# PPMB32-E.net
KiCad netlist of a schematic drawn in EAGLE
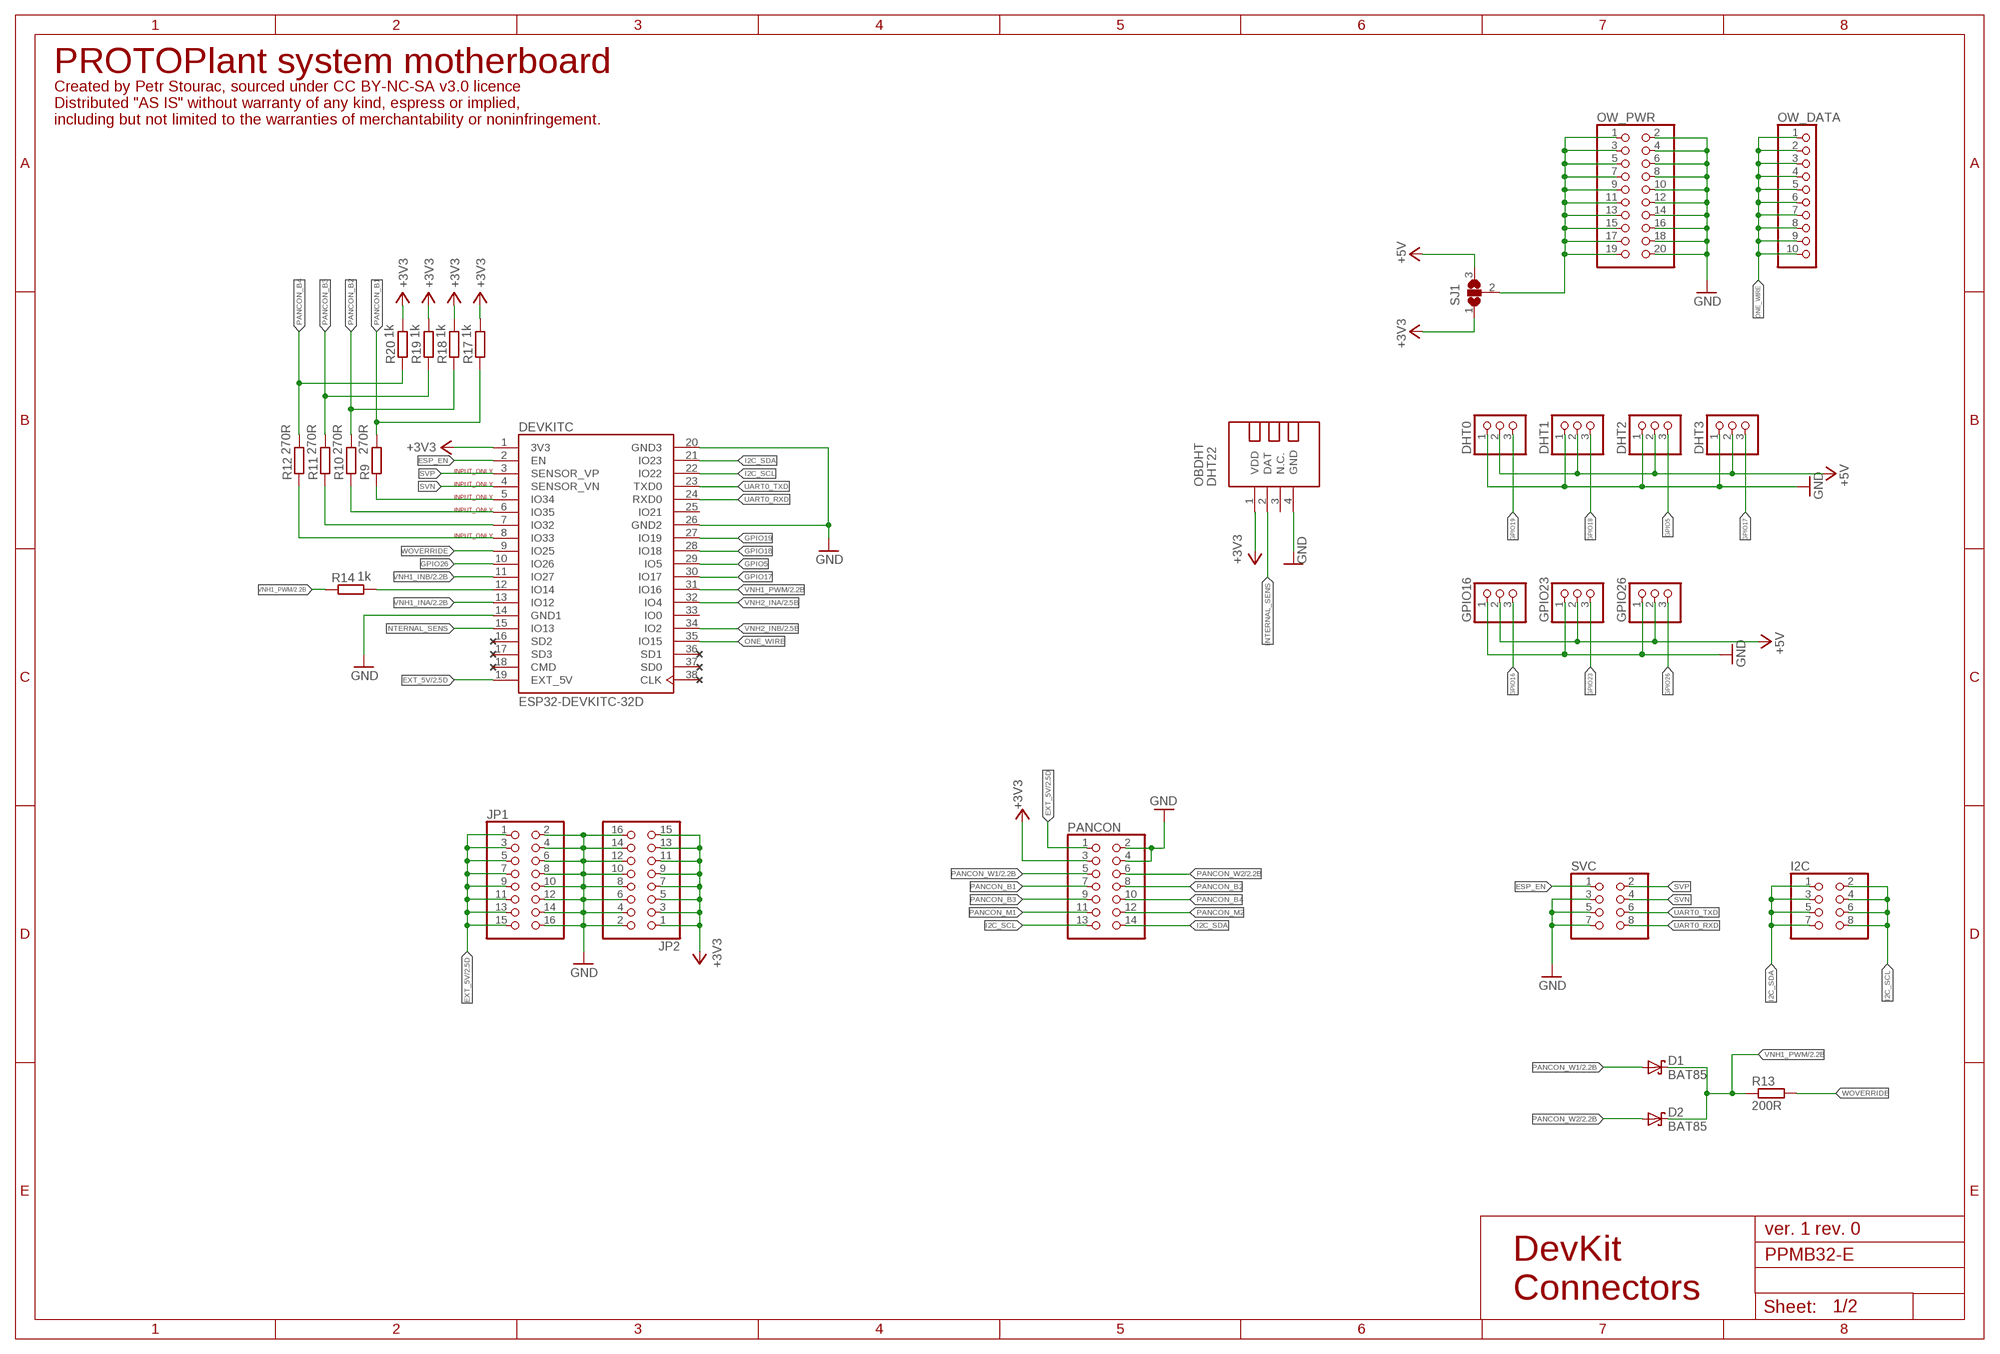
[diagram p0: schematic, sheet 1]
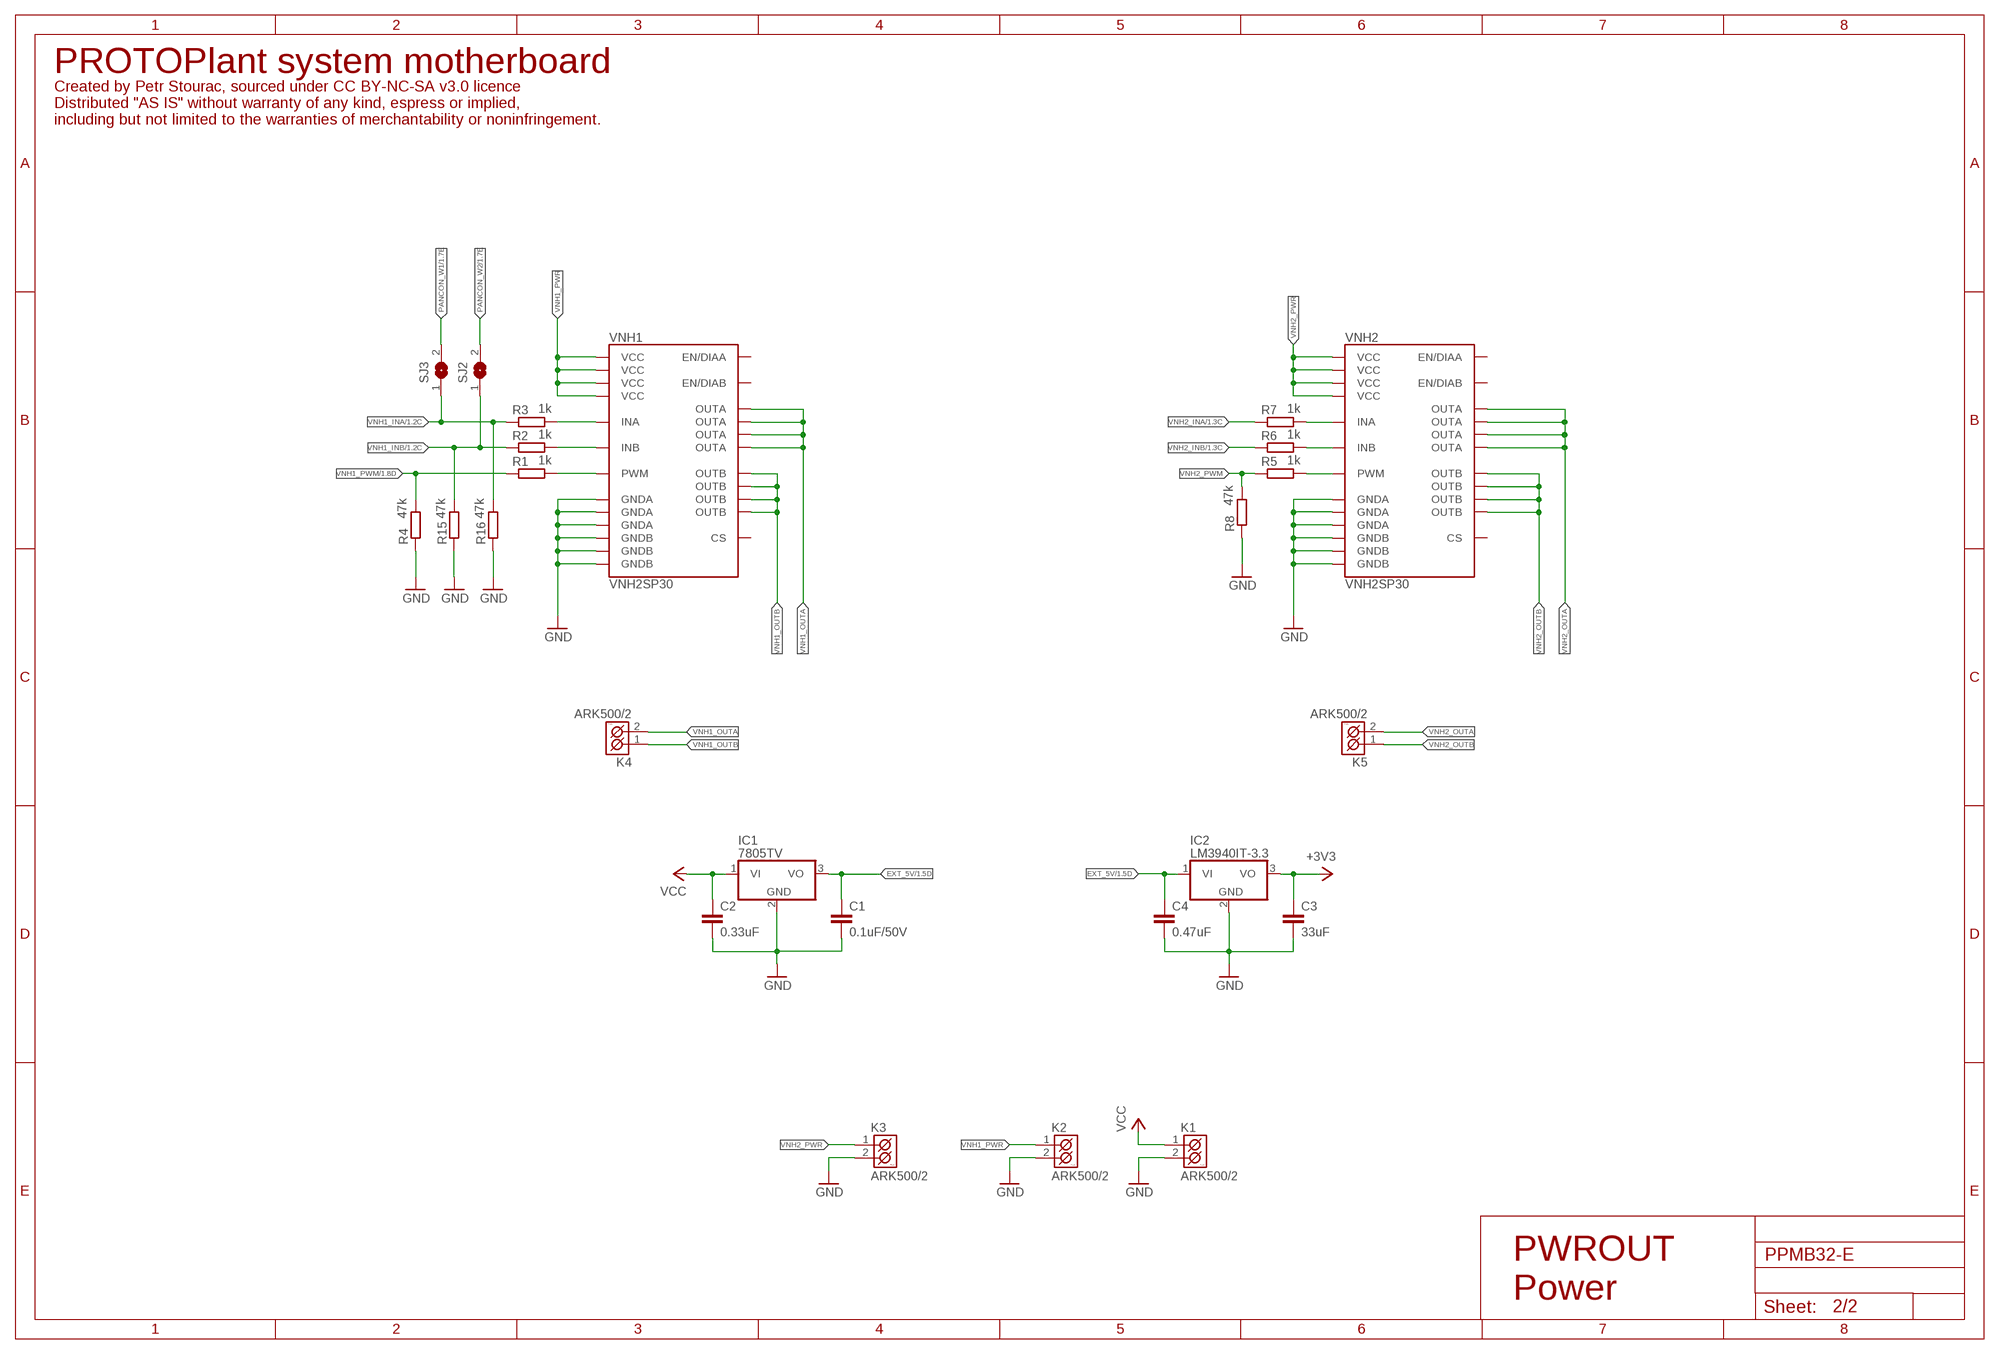
[diagram p1: schematic, sheet 2]

(export (version "E")
  (design (tool "Eeschema 10.0.6"))
  (components
    (comp (ref "D1")
      (value "BAT85")
      (footprint "eagle-import:DO35-7")
      (libsource (lib "eagle-import") (part "SCHOTTKY-DIODEDO35-7"))
    )
    (comp (ref "D2")
      (value "BAT85")
      (footprint "eagle-import:DO35-7")
      (libsource (lib "eagle-import") (part "SCHOTTKY-DIODEDO35-7"))
    )
    (comp (ref "DEVKITC")
      (value "ESP32-DEVKITC-32D")
      (footprint "eagle-import:MODULE_ESP32-DEVKITC-32D")
      (fields (field (name "MF") "Espressif Systems"))
      (libsource (lib "eagle-import") (part "ESP32-DEVKITC-32D"))
    )
    (comp (ref "DHT0")
      (value "PINHD-1X3")
      (footprint "eagle-import:1X03")
      (libsource (lib "eagle-import") (part "PINHD-1X3"))
    )
    (comp (ref "DHT1")
      (value "PINHD-1X3")
      (footprint "eagle-import:1X03")
      (libsource (lib "eagle-import") (part "PINHD-1X3"))
    )
    (comp (ref "DHT2")
      (value "PINHD-1X3")
      (footprint "eagle-import:1X03")
      (libsource (lib "eagle-import") (part "PINHD-1X3"))
    )
    (comp (ref "DHT3")
      (value "PINHD-1X3")
      (footprint "eagle-import:1X03")
      (libsource (lib "eagle-import") (part "PINHD-1X3"))
    )
    (comp (ref "GPIO16")
      (value "PINHD-1X3")
      (footprint "eagle-import:1X03")
      (libsource (lib "eagle-import") (part "PINHD-1X3"))
    )
    (comp (ref "GPIO23")
      (value "PINHD-1X3")
      (footprint "eagle-import:1X03")
      (libsource (lib "eagle-import") (part "PINHD-1X3"))
    )
    (comp (ref "GPIO26")
      (value "PINHD-1X3")
      (footprint "eagle-import:1X03")
      (libsource (lib "eagle-import") (part "PINHD-1X3"))
    )
    (comp (ref "I2C")
      (value "PINHD-2X4")
      (footprint "eagle-import:2X04")
      (libsource (lib "eagle-import") (part "PINHD-2X4"))
    )
    (comp (ref "JP1")
      (value "PINHD-2X8")
      (footprint "eagle-import:2X08")
      (libsource (lib "eagle-import") (part "PINHD-2X8"))
    )
    (comp (ref "JP2")
      (value "PINHD-2X8")
      (footprint "eagle-import:2X08")
      (libsource (lib "eagle-import") (part "PINHD-2X8"))
    )
    (comp (ref "OBDHT")
      (value "DHT22")
      (footprint "eagle-import:TEMP-HUM-SENSOR-DHT22")
      (libsource (lib "eagle-import") (part "TEMP-HUM-SENSOR-DHT22"))
    )
    (comp (ref "OW_DATA")
      (value "PINHD-1X10")
      (footprint "eagle-import:1X10")
      (libsource (lib "eagle-import") (part "PINHD-1X10"))
    )
    (comp (ref "OW_PWR")
      (value "PINHD-2X10")
      (footprint "eagle-import:2X10")
      (libsource (lib "eagle-import") (part "PINHD-2X10"))
    )
    (comp (ref "PANCON")
      (value "PINHD-2X7")
      (footprint "eagle-import:2X07")
      (libsource (lib "eagle-import") (part "PINHD-2X7"))
    )
    (comp (ref "R9")
      (value "270R")
      (footprint "eagle-import:R0603")
      (libsource (lib "eagle-import") (part "R-EU_R0603"))
    )
    (comp (ref "R10")
      (value "270R")
      (footprint "eagle-import:R0603")
      (libsource (lib "eagle-import") (part "R-EU_R0603"))
    )
    (comp (ref "R11")
      (value "270R")
      (footprint "eagle-import:R0603")
      (libsource (lib "eagle-import") (part "R-EU_R0603"))
    )
    (comp (ref "R12")
      (value "270R")
      (footprint "eagle-import:R0603")
      (libsource (lib "eagle-import") (part "R-EU_R0603"))
    )
    (comp (ref "R13")
      (value "200R")
      (footprint "eagle-import:R0603")
      (libsource (lib "eagle-import") (part "R-EU_R0603"))
    )
    (comp (ref "R14")
      (value "1k")
      (footprint "eagle-import:R0603")
      (libsource (lib "eagle-import") (part "R-EU_R0603"))
    )
    (comp (ref "R17")
      (value "1k")
      (footprint "eagle-import:R0603")
      (libsource (lib "eagle-import") (part "R-EU_R0603"))
    )
    (comp (ref "R18")
      (value "1k")
      (footprint "eagle-import:R0603")
      (libsource (lib "eagle-import") (part "R-EU_R0603"))
    )
    (comp (ref "R19")
      (value "1k")
      (footprint "eagle-import:R0603")
      (libsource (lib "eagle-import") (part "R-EU_R0603"))
    )
    (comp (ref "R20")
      (value "1k")
      (footprint "eagle-import:R0603")
      (libsource (lib "eagle-import") (part "R-EU_R0603"))
    )
    (comp (ref "SJ1")
      (value "SJ2W")
      (footprint "eagle-import:SJ_2")
      (libsource (lib "eagle-import") (part "SJ2W"))
    )
    (comp (ref "SVC")
      (value "PINHD-2X4")
      (footprint "eagle-import:2X04")
      (libsource (lib "eagle-import") (part "PINHD-2X4"))
    )
    (comp (ref "C1")
      (value "0.1uF/50V")
      (footprint "eagle-import:C1206K")
      (libsource (lib "eagle-import") (part "C-EUC1206K"))
    )
    (comp (ref "C2")
      (value "0.33uF")
      (footprint "eagle-import:C1206K")
      (libsource (lib "eagle-import") (part "C-EUC1206K"))
    )
    (comp (ref "C3")
      (value "33uF")
      (footprint "eagle-import:C1206K")
      (libsource (lib "eagle-import") (part "C-EUC1206K"))
    )
    (comp (ref "C4")
      (value "0.47uF")
      (footprint "eagle-import:C1206K")
      (libsource (lib "eagle-import") (part "C-EUC1206K"))
    )
    (comp (ref "IC1")
      (value "7805TV")
      (footprint "eagle-import:TO220V")
      (libsource (lib "eagle-import") (part "78TV05"))
    )
    (comp (ref "IC2")
      (value "LM3940IT-3.3")
      (footprint "eagle-import:TO220V")
      (libsource (lib "eagle-import") (part "78TV8"))
    )
    (comp (ref "K1")
      (value "ARK500/2")
      (footprint "eagle-import:ARK500_2")
      (libsource (lib "eagle-import") (part "ARK500/2"))
    )
    (comp (ref "K2")
      (value "ARK500/2")
      (footprint "eagle-import:ARK500_2")
      (libsource (lib "eagle-import") (part "ARK500/2"))
    )
    (comp (ref "K3")
      (value "ARK500/2")
      (footprint "eagle-import:ARK500_2")
      (libsource (lib "eagle-import") (part "ARK500/2"))
    )
    (comp (ref "K4")
      (value "ARK500/2")
      (footprint "eagle-import:ARK500_2")
      (libsource (lib "eagle-import") (part "ARK500/2"))
    )
    (comp (ref "K5")
      (value "ARK500/2")
      (footprint "eagle-import:ARK500_2")
      (libsource (lib "eagle-import") (part "ARK500/2"))
    )
    (comp (ref "R1")
      (value "1k")
      (footprint "eagle-import:R0603")
      (libsource (lib "eagle-import") (part "R-EU_R0603"))
    )
    (comp (ref "R2")
      (value "1k")
      (footprint "eagle-import:R0603")
      (libsource (lib "eagle-import") (part "R-EU_R0603"))
    )
    (comp (ref "R3")
      (value "1k")
      (footprint "eagle-import:R0603")
      (libsource (lib "eagle-import") (part "R-EU_R0603"))
    )
    (comp (ref "R4")
      (value "47k")
      (footprint "eagle-import:R0603")
      (libsource (lib "eagle-import") (part "R-EU_R0603"))
    )
    (comp (ref "R5")
      (value "1k")
      (footprint "eagle-import:R0603")
      (libsource (lib "eagle-import") (part "R-EU_R0603"))
    )
    (comp (ref "R6")
      (value "1k")
      (footprint "eagle-import:R0603")
      (libsource (lib "eagle-import") (part "R-EU_R0603"))
    )
    (comp (ref "R7")
      (value "1k")
      (footprint "eagle-import:R0603")
      (libsource (lib "eagle-import") (part "R-EU_R0603"))
    )
    (comp (ref "R8")
      (value "47k")
      (footprint "eagle-import:R0603")
      (libsource (lib "eagle-import") (part "R-EU_R0603"))
    )
    (comp (ref "R15")
      (value "47k")
      (footprint "eagle-import:R0603")
      (libsource (lib "eagle-import") (part "R-EU_R0603"))
    )
    (comp (ref "R16")
      (value "47k")
      (footprint "eagle-import:R0603")
      (libsource (lib "eagle-import") (part "R-EU_R0603"))
    )
    (comp (ref "SJ2") (value "SJ") (footprint "eagle-import:SJ") (libsource (lib "eagle-import") (part "SJ")))
    (comp (ref "SJ3") (value "SJ") (footprint "eagle-import:SJ") (libsource (lib "eagle-import") (part "SJ")))
    (comp (ref "VNH1")
      (value "VNH2SP30")
      (footprint "eagle-import:VNH2SP30")
      (libsource (lib "eagle-import") (part "VNH2SP30"))
    )
    (comp (ref "VNH2")
      (value "VNH2SP30")
      (footprint "eagle-import:VNH2SP30")
      (libsource (lib "eagle-import") (part "VNH2SP30"))
    )
  )
  (nets
    (net (code "1") (name "+3V3") (class "Default")
      (node (ref "C3") (pin "1") (pinfunction "1_1") (pintype "passive"))
      (node (ref "DEVKITC") (pin "1") (pinfunction "3V3_1") (pintype "power_in"))
      (node (ref "IC2") (pin "3") (pinfunction "VO_3") (pintype "passive"))
      (node (ref "JP2") (pin "1") (pinfunction "1_1") (pintype "passive"))
      (node (ref "JP2") (pin "11") (pinfunction "11_11") (pintype "passive"))
      (node (ref "JP2") (pin "13") (pinfunction "13_13") (pintype "passive"))
      (node (ref "JP2") (pin "15") (pinfunction "15_15") (pintype "passive"))
      (node (ref "JP2") (pin "3") (pinfunction "3_3") (pintype "passive"))
      (node (ref "JP2") (pin "5") (pinfunction "5_5") (pintype "passive"))
      (node (ref "JP2") (pin "7") (pinfunction "7_7") (pintype "passive"))
      (node (ref "JP2") (pin "9") (pinfunction "9_9") (pintype "passive"))
      (node (ref "OBDHT") (pin "1") (pinfunction "VDD_1") (pintype "power_in"))
      (node (ref "PANCON") (pin "3") (pinfunction "3_3") (pintype "passive"))
      (node (ref "R17") (pin "2") (pinfunction "2_2") (pintype "passive"))
      (node (ref "R18") (pin "2") (pinfunction "2_2") (pintype "passive"))
      (node (ref "R19") (pin "2") (pinfunction "2_2") (pintype "passive"))
      (node (ref "R20") (pin "2") (pinfunction "2_2") (pintype "passive"))
      (node (ref "SJ1") (pin "1") (pinfunction "1_1") (pintype "passive"))
    )
    (net (code "2") (name "+5V") (class "Default")
      (node (ref "DHT0") (pin "2") (pinfunction "2_2") (pintype "passive"))
      (node (ref "DHT1") (pin "2") (pinfunction "2_2") (pintype "passive"))
      (node (ref "DHT2") (pin "2") (pinfunction "2_2") (pintype "passive"))
      (node (ref "DHT3") (pin "2") (pinfunction "2_2") (pintype "passive"))
      (node (ref "GPIO16") (pin "2") (pinfunction "2_2") (pintype "passive"))
      (node (ref "GPIO23") (pin "2") (pinfunction "2_2") (pintype "passive"))
      (node (ref "GPIO26") (pin "2") (pinfunction "2_2") (pintype "passive"))
      (node (ref "SJ1") (pin "3") (pinfunction "3_3") (pintype "passive"))
    )
    (net (code "3") (name "ESP_EN") (class "Default")
      (node (ref "DEVKITC") (pin "2") (pinfunction "EN_2") (pintype "input"))
      (node (ref "SVC") (pin "1") (pinfunction "1_1") (pintype "passive"))
    )
    (net (code "4") (name "EXT_5V") (class "Default")
      (node (ref "C1") (pin "1") (pinfunction "1_1") (pintype "passive"))
      (node (ref "C4") (pin "1") (pinfunction "1_1") (pintype "passive"))
      (node (ref "DEVKITC") (pin "19") (pinfunction "EXT_5V_19") (pintype "power_in"))
      (node (ref "IC1") (pin "3") (pinfunction "VO_3") (pintype "passive"))
      (node (ref "IC2") (pin "1") (pinfunction "VI_1") (pintype "input"))
      (node (ref "JP1") (pin "1") (pinfunction "1_1") (pintype "passive"))
      (node (ref "JP1") (pin "11") (pinfunction "11_11") (pintype "passive"))
      (node (ref "JP1") (pin "13") (pinfunction "13_13") (pintype "passive"))
      (node (ref "JP1") (pin "15") (pinfunction "15_15") (pintype "passive"))
      (node (ref "JP1") (pin "3") (pinfunction "3_3") (pintype "passive"))
      (node (ref "JP1") (pin "5") (pinfunction "5_5") (pintype "passive"))
      (node (ref "JP1") (pin "7") (pinfunction "7_7") (pintype "passive"))
      (node (ref "JP1") (pin "9") (pinfunction "9_9") (pintype "passive"))
      (node (ref "PANCON") (pin "1") (pinfunction "1_1") (pintype "passive"))
    )
    (net (code "5") (name "GND") (class "Default")
      (node (ref "C1") (pin "2") (pinfunction "2_2") (pintype "passive"))
      (node (ref "C2") (pin "2") (pinfunction "2_2") (pintype "passive"))
      (node (ref "C3") (pin "2") (pinfunction "2_2") (pintype "passive"))
      (node (ref "C4") (pin "2") (pinfunction "2_2") (pintype "passive"))
      (node (ref "DEVKITC") (pin "14") (pinfunction "GND1_14") (pintype "power_in"))
      (node (ref "DEVKITC") (pin "20") (pinfunction "GND3_20") (pintype "power_in"))
      (node (ref "DEVKITC") (pin "26") (pinfunction "GND2_26") (pintype "power_in"))
      (node (ref "DHT0") (pin "1") (pinfunction "1_1") (pintype "passive"))
      (node (ref "DHT1") (pin "1") (pinfunction "1_1") (pintype "passive"))
      (node (ref "DHT2") (pin "1") (pinfunction "1_1") (pintype "passive"))
      (node (ref "DHT3") (pin "1") (pinfunction "1_1") (pintype "passive"))
      (node (ref "GPIO16") (pin "1") (pinfunction "1_1") (pintype "passive"))
      (node (ref "GPIO23") (pin "1") (pinfunction "1_1") (pintype "passive"))
      (node (ref "GPIO26") (pin "1") (pinfunction "1_1") (pintype "passive"))
      (node (ref "IC1") (pin "2") (pinfunction "GND_2") (pintype "passive"))
      (node (ref "IC2") (pin "2") (pinfunction "GND_2") (pintype "passive"))
      (node (ref "JP1") (pin "10") (pinfunction "10_10") (pintype "passive"))
      (node (ref "JP1") (pin "12") (pinfunction "12_12") (pintype "passive"))
      (node (ref "JP1") (pin "14") (pinfunction "14_14") (pintype "passive"))
      (node (ref "JP1") (pin "16") (pinfunction "16_16") (pintype "passive"))
      (node (ref "JP1") (pin "2") (pinfunction "2_2") (pintype "passive"))
      (node (ref "JP1") (pin "4") (pinfunction "4_4") (pintype "passive"))
      (node (ref "JP1") (pin "6") (pinfunction "6_6") (pintype "passive"))
      (node (ref "JP1") (pin "8") (pinfunction "8_8") (pintype "passive"))
      (node (ref "JP2") (pin "10") (pinfunction "10_10") (pintype "passive"))
      (node (ref "JP2") (pin "12") (pinfunction "12_12") (pintype "passive"))
      (node (ref "JP2") (pin "14") (pinfunction "14_14") (pintype "passive"))
      (node (ref "JP2") (pin "16") (pinfunction "16_16") (pintype "passive"))
      (node (ref "JP2") (pin "2") (pinfunction "2_2") (pintype "passive"))
      (node (ref "JP2") (pin "4") (pinfunction "4_4") (pintype "passive"))
      (node (ref "JP2") (pin "6") (pinfunction "6_6") (pintype "passive"))
      (node (ref "JP2") (pin "8") (pinfunction "8_8") (pintype "passive"))
      (node (ref "K1") (pin "2") (pinfunction "K2_2") (pintype "passive"))
      (node (ref "K2") (pin "2") (pinfunction "K2_2") (pintype "passive"))
      (node (ref "K3") (pin "2") (pinfunction "K2_2") (pintype "passive"))
      (node (ref "OBDHT") (pin "4") (pinfunction "GND_4") (pintype "power_in"))
      (node (ref "OW_PWR") (pin "10") (pinfunction "10_10") (pintype "passive"))
      (node (ref "OW_PWR") (pin "12") (pinfunction "12_12") (pintype "passive"))
      (node (ref "OW_PWR") (pin "14") (pinfunction "14_14") (pintype "passive"))
      (node (ref "OW_PWR") (pin "16") (pinfunction "16_16") (pintype "passive"))
      (node (ref "OW_PWR") (pin "18") (pinfunction "18_18") (pintype "passive"))
      (node (ref "OW_PWR") (pin "2") (pinfunction "2_2") (pintype "passive"))
      (node (ref "OW_PWR") (pin "20") (pinfunction "20_20") (pintype "passive"))
      (node (ref "OW_PWR") (pin "4") (pinfunction "4_4") (pintype "passive"))
      (node (ref "OW_PWR") (pin "6") (pinfunction "6_6") (pintype "passive"))
      (node (ref "OW_PWR") (pin "8") (pinfunction "8_8") (pintype "passive"))
      (node (ref "PANCON") (pin "2") (pinfunction "2_2") (pintype "passive"))
      (node (ref "PANCON") (pin "4") (pinfunction "4_4") (pintype "passive"))
      (node (ref "R15") (pin "1") (pinfunction "1_1") (pintype "passive"))
      (node (ref "R16") (pin "1") (pinfunction "1_1") (pintype "passive"))
      (node (ref "R4") (pin "1") (pinfunction "1_1") (pintype "passive"))
      (node (ref "R8") (pin "1") (pinfunction "1_1") (pintype "passive"))
      (node (ref "SVC") (pin "3") (pinfunction "3_3") (pintype "passive"))
      (node (ref "SVC") (pin "5") (pinfunction "5_5") (pintype "passive"))
      (node (ref "SVC") (pin "7") (pinfunction "7_7") (pintype "passive"))
      (node (ref "VNH1") (pin "18") (pinfunction "GNDB_18") (pintype "bidirectional"))
      (node (ref "VNH1") (pin "19") (pinfunction "GNDB_19") (pintype "bidirectional"))
      (node (ref "VNH1") (pin "20") (pinfunction "GNDB_20") (pintype "bidirectional"))
      (node (ref "VNH1") (pin "26") (pinfunction "GNDA_26") (pintype "bidirectional"))
      (node (ref "VNH1") (pin "27") (pinfunction "GNDA_27") (pintype "bidirectional"))
      (node (ref "VNH1") (pin "28") (pinfunction "GNDA_28") (pintype "bidirectional"))
      (node (ref "VNH2") (pin "18") (pinfunction "GNDB_18") (pintype "bidirectional"))
      (node (ref "VNH2") (pin "19") (pinfunction "GNDB_19") (pintype "bidirectional"))
      (node (ref "VNH2") (pin "20") (pinfunction "GNDB_20") (pintype "bidirectional"))
      (node (ref "VNH2") (pin "26") (pinfunction "GNDA_26") (pintype "bidirectional"))
      (node (ref "VNH2") (pin "27") (pinfunction "GNDA_27") (pintype "bidirectional"))
      (node (ref "VNH2") (pin "28") (pinfunction "GNDA_28") (pintype "bidirectional"))
    )
    (net (code "6") (name "GPIO5") (class "Default")
      (node (ref "DEVKITC") (pin "29") (pinfunction "IO5_29") (pintype "bidirectional"))
      (node (ref "DHT2") (pin "3") (pinfunction "3_3") (pintype "passive"))
    )
    (net (code "7") (name "GPIO16") (class "Default")
      (node (ref "GPIO16") (pin "3") (pinfunction "3_3") (pintype "passive"))
    )
    (net (code "8") (name "GPIO17") (class "Default")
      (node (ref "DEVKITC") (pin "30") (pinfunction "IO17_30") (pintype "bidirectional"))
      (node (ref "DHT3") (pin "3") (pinfunction "3_3") (pintype "passive"))
    )
    (net (code "9") (name "GPIO18") (class "Default")
      (node (ref "DEVKITC") (pin "28") (pinfunction "IO18_28") (pintype "bidirectional"))
      (node (ref "DHT1") (pin "3") (pinfunction "3_3") (pintype "passive"))
    )
    (net (code "10") (name "GPIO19") (class "Default")
      (node (ref "DEVKITC") (pin "27") (pinfunction "IO19_27") (pintype "bidirectional"))
      (node (ref "DHT0") (pin "3") (pinfunction "3_3") (pintype "passive"))
    )
    (net (code "11") (name "GPIO23") (class "Default")
      (node (ref "GPIO23") (pin "3") (pinfunction "3_3") (pintype "passive"))
    )
    (net (code "12") (name "GPIO26") (class "Default")
      (node (ref "DEVKITC") (pin "10") (pinfunction "IO26_10") (pintype "bidirectional"))
      (node (ref "GPIO26") (pin "3") (pinfunction "3_3") (pintype "passive"))
    )
    (net (code "13") (name "I2C_SCL") (class "Default")
      (node (ref "DEVKITC") (pin "22") (pinfunction "IO22_22") (pintype "bidirectional"))
      (node (ref "I2C") (pin "2") (pinfunction "2_2") (pintype "passive"))
      (node (ref "I2C") (pin "4") (pinfunction "4_4") (pintype "passive"))
      (node (ref "I2C") (pin "6") (pinfunction "6_6") (pintype "passive"))
      (node (ref "I2C") (pin "8") (pinfunction "8_8") (pintype "passive"))
      (node (ref "PANCON") (pin "13") (pinfunction "13_13") (pintype "passive"))
    )
    (net (code "14") (name "I2C_SDA") (class "Default")
      (node (ref "DEVKITC") (pin "21") (pinfunction "IO23_21") (pintype "bidirectional"))
      (node (ref "I2C") (pin "1") (pinfunction "1_1") (pintype "passive"))
      (node (ref "I2C") (pin "3") (pinfunction "3_3") (pintype "passive"))
      (node (ref "I2C") (pin "5") (pinfunction "5_5") (pintype "passive"))
      (node (ref "I2C") (pin "7") (pinfunction "7_7") (pintype "passive"))
      (node (ref "PANCON") (pin "14") (pinfunction "14_14") (pintype "passive"))
    )
    (net (code "15") (name "INTERNAL_SENS") (class "Default")
      (node (ref "DEVKITC") (pin "15") (pinfunction "IO13_15") (pintype "bidirectional"))
      (node (ref "OBDHT") (pin "2") (pinfunction "DAT_2") (pintype "bidirectional"))
    )
    (net (code "16") (name "Net-(DEVKITC-IO14)") (class "Default")
      (node (ref "DEVKITC") (pin "12") (pinfunction "IO14_12") (pintype "bidirectional"))
      (node (ref "R14") (pin "2") (pinfunction "2_2") (pintype "passive"))
    )
    (net (code "17") (name "Net-(DEVKITC-IO32)") (class "Default")
      (node (ref "DEVKITC") (pin "7") (pinfunction "IO32_7") (pintype "bidirectional"))
      (node (ref "R11") (pin "1") (pinfunction "1_1") (pintype "passive"))
    )
    (net (code "18") (name "Net-(DEVKITC-IO33)") (class "Default")
      (node (ref "DEVKITC") (pin "8") (pinfunction "IO33_8") (pintype "bidirectional"))
      (node (ref "R12") (pin "1") (pinfunction "1_1") (pintype "passive"))
    )
    (net (code "19") (name "Net-(DEVKITC-IO34)") (class "Default")
      (node (ref "DEVKITC") (pin "5") (pinfunction "IO34_5") (pintype "bidirectional"))
      (node (ref "R9") (pin "1") (pinfunction "1_1") (pintype "passive"))
    )
    (net (code "20") (name "Net-(DEVKITC-IO35)") (class "Default")
      (node (ref "DEVKITC") (pin "6") (pinfunction "IO35_6") (pintype "bidirectional"))
      (node (ref "R10") (pin "1") (pinfunction "1_1") (pintype "passive"))
    )
    (net (code "21") (name "Net-(OW_PWR-Pad1)") (class "Default")
      (node (ref "OW_PWR") (pin "1") (pinfunction "1_1") (pintype "passive"))
      (node (ref "OW_PWR") (pin "11") (pinfunction "11_11") (pintype "passive"))
      (node (ref "OW_PWR") (pin "13") (pinfunction "13_13") (pintype "passive"))
      (node (ref "OW_PWR") (pin "15") (pinfunction "15_15") (pintype "passive"))
      (node (ref "OW_PWR") (pin "17") (pinfunction "17_17") (pintype "passive"))
      (node (ref "OW_PWR") (pin "19") (pinfunction "19_19") (pintype "passive"))
      (node (ref "OW_PWR") (pin "3") (pinfunction "3_3") (pintype "passive"))
      (node (ref "OW_PWR") (pin "5") (pinfunction "5_5") (pintype "passive"))
      (node (ref "OW_PWR") (pin "7") (pinfunction "7_7") (pintype "passive"))
      (node (ref "OW_PWR") (pin "9") (pinfunction "9_9") (pintype "passive"))
      (node (ref "SJ1") (pin "2") (pinfunction "2_2") (pintype "passive"))
    )
    (net (code "22") (name "Net-(VNH1-INA)") (class "Default")
      (node (ref "R3") (pin "2") (pinfunction "2_2") (pintype "passive"))
      (node (ref "VNH1") (pin "5") (pinfunction "INA_5") (pintype "bidirectional"))
    )
    (net (code "23") (name "Net-(VNH1-INB)") (class "Default")
      (node (ref "R2") (pin "2") (pinfunction "2_2") (pintype "passive"))
      (node (ref "VNH1") (pin "11") (pinfunction "INB_11") (pintype "bidirectional"))
    )
    (net (code "24") (name "Net-(VNH1-PWM)") (class "Default")
      (node (ref "R1") (pin "2") (pinfunction "2_2") (pintype "passive"))
      (node (ref "VNH1") (pin "8") (pinfunction "PWM_8") (pintype "bidirectional"))
    )
    (net (code "25") (name "Net-(VNH2-INA)") (class "Default")
      (node (ref "R7") (pin "2") (pinfunction "2_2") (pintype "passive"))
      (node (ref "VNH2") (pin "5") (pinfunction "INA_5") (pintype "bidirectional"))
    )
    (net (code "26") (name "Net-(VNH2-INB)") (class "Default")
      (node (ref "R6") (pin "2") (pinfunction "2_2") (pintype "passive"))
      (node (ref "VNH2") (pin "11") (pinfunction "INB_11") (pintype "bidirectional"))
    )
    (net (code "27") (name "Net-(VNH2-PWM)") (class "Default")
      (node (ref "R5") (pin "2") (pinfunction "2_2") (pintype "passive"))
      (node (ref "VNH2") (pin "8") (pinfunction "PWM_8") (pintype "bidirectional"))
    )
    (net (code "28") (name "ONE_WIRE") (class "Default")
      (node (ref "DEVKITC") (pin "35") (pinfunction "IO15_35") (pintype "bidirectional"))
      (node (ref "OW_DATA") (pin "1") (pinfunction "1_1") (pintype "passive"))
      (node (ref "OW_DATA") (pin "10") (pinfunction "10_10") (pintype "passive"))
      (node (ref "OW_DATA") (pin "2") (pinfunction "2_2") (pintype "passive"))
      (node (ref "OW_DATA") (pin "3") (pinfunction "3_3") (pintype "passive"))
      (node (ref "OW_DATA") (pin "4") (pinfunction "4_4") (pintype "passive"))
      (node (ref "OW_DATA") (pin "5") (pinfunction "5_5") (pintype "passive"))
      (node (ref "OW_DATA") (pin "6") (pinfunction "6_6") (pintype "passive"))
      (node (ref "OW_DATA") (pin "7") (pinfunction "7_7") (pintype "passive"))
      (node (ref "OW_DATA") (pin "8") (pinfunction "8_8") (pintype "passive"))
      (node (ref "OW_DATA") (pin "9") (pinfunction "9_9") (pintype "passive"))
    )
    (net (code "29") (name "PANCON_B1") (class "Default")
      (node (ref "PANCON") (pin "7") (pinfunction "7_7") (pintype "passive"))
      (node (ref "R17") (pin "1") (pinfunction "1_1") (pintype "passive"))
      (node (ref "R9") (pin "2") (pinfunction "2_2") (pintype "passive"))
    )
    (net (code "30") (name "PANCON_B2") (class "Default")
      (node (ref "PANCON") (pin "8") (pinfunction "8_8") (pintype "passive"))
      (node (ref "R10") (pin "2") (pinfunction "2_2") (pintype "passive"))
      (node (ref "R18") (pin "1") (pinfunction "1_1") (pintype "passive"))
    )
    (net (code "31") (name "PANCON_B3") (class "Default")
      (node (ref "PANCON") (pin "9") (pinfunction "9_9") (pintype "passive"))
      (node (ref "R11") (pin "2") (pinfunction "2_2") (pintype "passive"))
      (node (ref "R19") (pin "1") (pinfunction "1_1") (pintype "passive"))
    )
    (net (code "32") (name "PANCON_B4") (class "Default")
      (node (ref "PANCON") (pin "10") (pinfunction "10_10") (pintype "passive"))
      (node (ref "R12") (pin "2") (pinfunction "2_2") (pintype "passive"))
      (node (ref "R20") (pin "1") (pinfunction "1_1") (pintype "passive"))
    )
    (net (code "33") (name "PANCON_M1") (class "Default")
      (node (ref "PANCON") (pin "11") (pinfunction "11_11") (pintype "passive"))
    )
    (net (code "34") (name "PANCON_M2") (class "Default")
      (node (ref "PANCON") (pin "12") (pinfunction "12_12") (pintype "passive"))
    )
    (net (code "35") (name "PANCON_W1") (class "Default")
      (node (ref "D1") (pin "A") (pinfunction "A_A") (pintype "passive"))
      (node (ref "PANCON") (pin "5") (pinfunction "5_5") (pintype "passive"))
      (node (ref "SJ3") (pin "2") (pinfunction "2_2") (pintype "passive"))
    )
    (net (code "36") (name "PANCON_W2") (class "Default")
      (node (ref "D2") (pin "A") (pinfunction "A_A") (pintype "passive"))
      (node (ref "PANCON") (pin "6") (pinfunction "6_6") (pintype "passive"))
      (node (ref "SJ2") (pin "2") (pinfunction "2_2") (pintype "passive"))
    )
    (net (code "37") (name "SVN") (class "Default")
      (node (ref "DEVKITC") (pin "4") (pinfunction "SENSOR_VN_4") (pintype "input"))
      (node (ref "SVC") (pin "4") (pinfunction "4_4") (pintype "passive"))
    )
    (net (code "38") (name "SVP") (class "Default")
      (node (ref "DEVKITC") (pin "3") (pinfunction "SENSOR_VP_3") (pintype "input"))
      (node (ref "SVC") (pin "2") (pinfunction "2_2") (pintype "passive"))
    )
    (net (code "39") (name "UART0_RXD") (class "Default")
      (node (ref "DEVKITC") (pin "24") (pinfunction "RXD0_24") (pintype "input"))
      (node (ref "SVC") (pin "8") (pinfunction "8_8") (pintype "passive"))
    )
    (net (code "40") (name "UART0_TXD") (class "Default")
      (node (ref "DEVKITC") (pin "23") (pinfunction "TXD0_23") (pintype "output"))
      (node (ref "SVC") (pin "6") (pinfunction "6_6") (pintype "passive"))
    )
    (net (code "41") (name "VCC") (class "Default")
      (node (ref "C2") (pin "1") (pinfunction "1_1") (pintype "passive"))
      (node (ref "IC1") (pin "1") (pinfunction "VI_1") (pintype "input"))
      (node (ref "K1") (pin "1") (pinfunction "K1_1") (pintype "passive"))
    )
    (net (code "42") (name "VNH1_INA") (class "Default")
      (node (ref "DEVKITC") (pin "13") (pinfunction "IO12_13") (pintype "bidirectional"))
      (node (ref "R16") (pin "2") (pinfunction "2_2") (pintype "passive"))
      (node (ref "R3") (pin "1") (pinfunction "1_1") (pintype "passive"))
      (node (ref "SJ3") (pin "1") (pinfunction "1_1") (pintype "passive"))
    )
    (net (code "43") (name "VNH1_INB") (class "Default")
      (node (ref "DEVKITC") (pin "11") (pinfunction "IO27_11") (pintype "bidirectional"))
      (node (ref "R15") (pin "2") (pinfunction "2_2") (pintype "passive"))
      (node (ref "R2") (pin "1") (pinfunction "1_1") (pintype "passive"))
      (node (ref "SJ2") (pin "1") (pinfunction "1_1") (pintype "passive"))
    )
    (net (code "44") (name "VNH1_OUTA") (class "Default")
      (node (ref "K4") (pin "2") (pinfunction "K2_2") (pintype "passive"))
      (node (ref "VNH1") (pin "1") (pinfunction "OUTA_1") (pintype "bidirectional"))
      (node (ref "VNH1") (pin "25") (pinfunction "OUTA_25") (pintype "bidirectional"))
      (node (ref "VNH1") (pin "30") (pinfunction "OUTA_30") (pintype "bidirectional"))
      (node (ref "VNH1") (pin "SLUG3") (pinfunction "OUTA_SLUG3") (pintype "bidirectional"))
    )
    (net (code "45") (name "VNH1_OUTB") (class "Default")
      (node (ref "K4") (pin "1") (pinfunction "K1_1") (pintype "passive"))
      (node (ref "VNH1") (pin "15") (pinfunction "OUTB_15") (pintype "bidirectional"))
      (node (ref "VNH1") (pin "16") (pinfunction "OUTB_16") (pintype "bidirectional"))
      (node (ref "VNH1") (pin "21") (pinfunction "OUTB_21") (pintype "bidirectional"))
      (node (ref "VNH1") (pin "SLUG2") (pinfunction "OUTB_SLUG2") (pintype "bidirectional"))
    )
    (net (code "46") (name "VNH1_PWM") (class "Default")
      (node (ref "D1") (pin "C") (pinfunction "C_C") (pintype "passive"))
      (node (ref "D2") (pin "C") (pinfunction "C_C") (pintype "passive"))
      (node (ref "DEVKITC") (pin "31") (pinfunction "IO16_31") (pintype "bidirectional"))
      (node (ref "R1") (pin "1") (pinfunction "1_1") (pintype "passive"))
      (node (ref "R13") (pin "1") (pinfunction "1_1") (pintype "passive"))
      (node (ref "R14") (pin "1") (pinfunction "1_1") (pintype "passive"))
      (node (ref "R4") (pin "2") (pinfunction "2_2") (pintype "passive"))
    )
    (net (code "47") (name "VNH1_PWR") (class "Default")
      (node (ref "K2") (pin "1") (pinfunction "K1_1") (pintype "passive"))
      (node (ref "VNH1") (pin "13") (pinfunction "VCC_13") (pintype "bidirectional"))
      (node (ref "VNH1") (pin "23") (pinfunction "VCC_23") (pintype "bidirectional"))
      (node (ref "VNH1") (pin "3") (pinfunction "VCC_3") (pintype "bidirectional"))
      (node (ref "VNH1") (pin "SLUG1") (pinfunction "VCC_SLUG1") (pintype "bidirectional"))
    )
    (net (code "48") (name "VNH2_INA") (class "Default")
      (node (ref "DEVKITC") (pin "32") (pinfunction "IO4_32") (pintype "bidirectional"))
      (node (ref "R7") (pin "1") (pinfunction "1_1") (pintype "passive"))
    )
    (net (code "49") (name "VNH2_INB") (class "Default")
      (node (ref "DEVKITC") (pin "34") (pinfunction "IO2_34") (pintype "bidirectional"))
      (node (ref "R6") (pin "1") (pinfunction "1_1") (pintype "passive"))
    )
    (net (code "50") (name "VNH2_OUTA") (class "Default")
      (node (ref "K5") (pin "2") (pinfunction "K2_2") (pintype "passive"))
      (node (ref "VNH2") (pin "1") (pinfunction "OUTA_1") (pintype "bidirectional"))
      (node (ref "VNH2") (pin "25") (pinfunction "OUTA_25") (pintype "bidirectional"))
      (node (ref "VNH2") (pin "30") (pinfunction "OUTA_30") (pintype "bidirectional"))
      (node (ref "VNH2") (pin "SLUG3") (pinfunction "OUTA_SLUG3") (pintype "bidirectional"))
    )
    (net (code "51") (name "VNH2_OUTB") (class "Default")
      (node (ref "K5") (pin "1") (pinfunction "K1_1") (pintype "passive"))
      (node (ref "VNH2") (pin "15") (pinfunction "OUTB_15") (pintype "bidirectional"))
      (node (ref "VNH2") (pin "16") (pinfunction "OUTB_16") (pintype "bidirectional"))
      (node (ref "VNH2") (pin "21") (pinfunction "OUTB_21") (pintype "bidirectional"))
      (node (ref "VNH2") (pin "SLUG2") (pinfunction "OUTB_SLUG2") (pintype "bidirectional"))
    )
    (net (code "52") (name "VNH2_PWM") (class "Default")
      (node (ref "R5") (pin "1") (pinfunction "1_1") (pintype "passive"))
      (node (ref "R8") (pin "2") (pinfunction "2_2") (pintype "passive"))
    )
    (net (code "53") (name "VNH2_PWR") (class "Default")
      (node (ref "K3") (pin "1") (pinfunction "K1_1") (pintype "passive"))
      (node (ref "VNH2") (pin "13") (pinfunction "VCC_13") (pintype "bidirectional"))
      (node (ref "VNH2") (pin "23") (pinfunction "VCC_23") (pintype "bidirectional"))
      (node (ref "VNH2") (pin "3") (pinfunction "VCC_3") (pintype "bidirectional"))
      (node (ref "VNH2") (pin "SLUG1") (pinfunction "VCC_SLUG1") (pintype "bidirectional"))
    )
    (net (code "54") (name "WOVERRIDE") (class "Default")
      (node (ref "DEVKITC") (pin "9") (pinfunction "IO25_9") (pintype "bidirectional"))
      (node (ref "R13") (pin "2") (pinfunction "2_2") (pintype "passive"))
    )
    (net (code "55") (name "unconnected-(DEVKITC-CLK-Pad38)") (class "Default")
      (node (ref "DEVKITC") (pin "38") (pinfunction "CLK_38") (pintype "input"))
    )
    (net (code "56") (name "unconnected-(DEVKITC-CMD-Pad18)") (class "Default")
      (node (ref "DEVKITC") (pin "18") (pinfunction "CMD_18") (pintype "bidirectional"))
    )
    (net (code "57") (name "unconnected-(DEVKITC-IO0-Pad33)") (class "Default")
      (node (ref "DEVKITC") (pin "33") (pinfunction "IO0_33") (pintype "bidirectional"))
    )
    (net (code "58") (name "unconnected-(DEVKITC-IO21-Pad25)") (class "Default")
      (node (ref "DEVKITC") (pin "25") (pinfunction "IO21_25") (pintype "bidirectional"))
    )
    (net (code "59") (name "unconnected-(DEVKITC-SD0-Pad37)") (class "Default")
      (node (ref "DEVKITC") (pin "37") (pinfunction "SD0_37") (pintype "bidirectional"))
    )
    (net (code "60") (name "unconnected-(DEVKITC-SD1-Pad36)") (class "Default")
      (node (ref "DEVKITC") (pin "36") (pinfunction "SD1_36") (pintype "bidirectional"))
    )
    (net (code "61") (name "unconnected-(DEVKITC-SD2-Pad16)") (class "Default")
      (node (ref "DEVKITC") (pin "16") (pinfunction "SD2_16") (pintype "bidirectional"))
    )
    (net (code "62") (name "unconnected-(DEVKITC-SD3-Pad17)") (class "Default")
      (node (ref "DEVKITC") (pin "17") (pinfunction "SD3_17") (pintype "bidirectional"))
    )
    (net (code "63") (name "unconnected-(OBDHT-N.C.-Pad3)") (class "Default")
      (node (ref "OBDHT") (pin "3") (pinfunction "N.C._3") (pintype "passive"))
    )
    (net (code "64") (name "unconnected-(VNH1-CS-Pad9)") (class "Default")
      (node (ref "VNH1") (pin "9") (pinfunction "CS_9") (pintype "bidirectional"))
    )
    (net (code "65") (name "unconnected-(VNH1-EN{slash}DIAA-Pad6)") (class "Default")
      (node (ref "VNH1") (pin "6") (pinfunction "EN/DIAA_6") (pintype "bidirectional"))
    )
    (net (code "66") (name "unconnected-(VNH1-EN{slash}DIAB-Pad10)") (class "Default")
      (node (ref "VNH1") (pin "10") (pinfunction "EN/DIAB_10") (pintype "bidirectional"))
    )
    (net (code "67") (name "unconnected-(VNH2-CS-Pad9)") (class "Default")
      (node (ref "VNH2") (pin "9") (pinfunction "CS_9") (pintype "bidirectional"))
    )
    (net (code "68") (name "unconnected-(VNH2-EN{slash}DIAA-Pad6)") (class "Default")
      (node (ref "VNH2") (pin "6") (pinfunction "EN/DIAA_6") (pintype "bidirectional"))
    )
    (net (code "69") (name "unconnected-(VNH2-EN{slash}DIAB-Pad10)") (class "Default")
      (node (ref "VNH2") (pin "10") (pinfunction "EN/DIAB_10") (pintype "bidirectional"))
    )
  )
)
